# DEPDisc_Base_rev1_v4.net
KiCad netlist of a schematic drawn in EAGLE
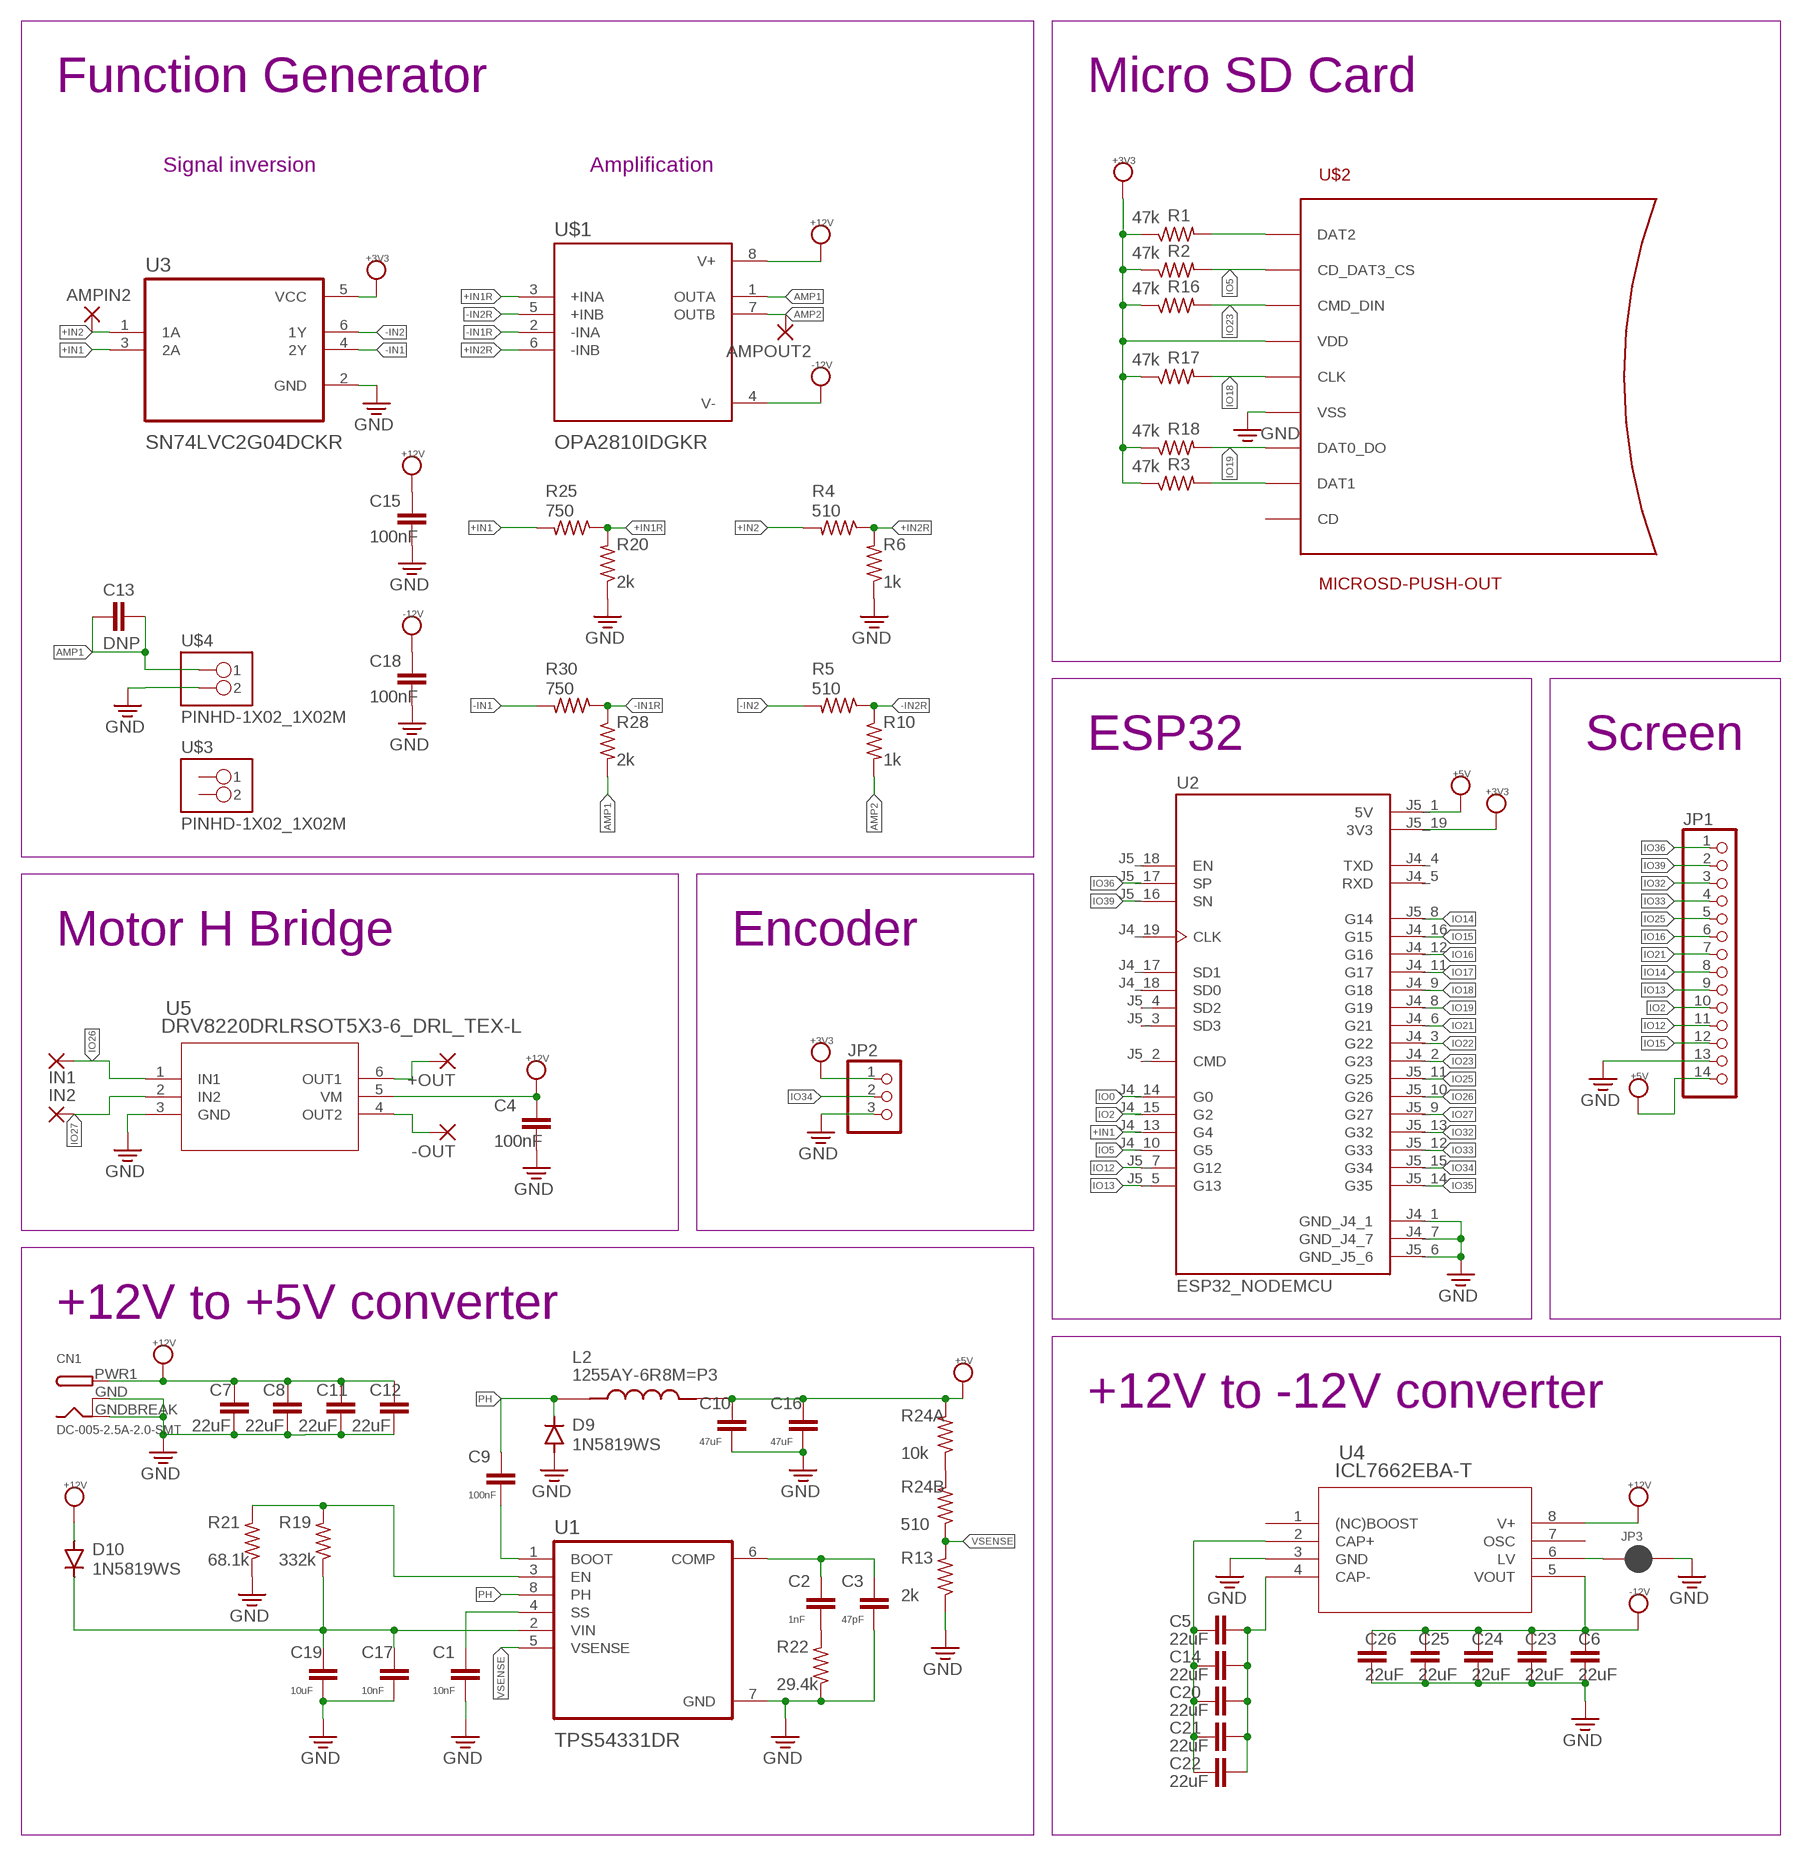
[diagram p0: schematic, sheet 1]

(export (version "E")
  (design (tool "Eeschema 10.0.6"))
  (components
    (comp (ref "+OUT")
      (value "2,54/1,1")
      (footprint "eagle-import:2,54_1,1")
      (libsource (lib "eagle-import") (part "2,54/1,1"))
    )
    (comp (ref "-OUT")
      (value "2,54/1,1")
      (footprint "eagle-import:2,54_1,1")
      (libsource (lib "eagle-import") (part "2,54/1,1"))
    )
    (comp (ref "AMPIN2")
      (value "1,6/0,8")
      (footprint "eagle-import:1,6_0,8")
      (libsource (lib "eagle-import") (part "1,6/0,8"))
    )
    (comp (ref "AMPOUT2")
      (value "1,6/0,8")
      (footprint "eagle-import:1,6_0,8")
      (libsource (lib "eagle-import") (part "1,6/0,8"))
    )
    (comp (ref "C1")
      (value "10nF")
      (footprint "eagle-import:C0603K")
      (libsource (lib "eagle-import") (part "resistor_348_C-EUC0603K"))
    )
    (comp (ref "C2")
      (value "1nF")
      (footprint "eagle-import:C0603K")
      (libsource (lib "eagle-import") (part "resistor_348_C-EUC0603K"))
    )
    (comp (ref "C3")
      (value "47pF")
      (footprint "eagle-import:C0603K")
      (libsource (lib "eagle-import") (part "resistor_348_C-EUC0603K"))
    )
    (comp (ref "C4")
      (value "100nF")
      (footprint "eagle-import:C0603K")
      (libsource (lib "eagle-import") (part "C-EUC0603K"))
    )
    (comp (ref "C5")
      (value "22uF")
      (footprint "eagle-import:C0805K")
      (libsource (lib "eagle-import") (part "C-EUC0805K"))
    )
    (comp (ref "C6")
      (value "22uF")
      (footprint "eagle-import:C0805K")
      (libsource (lib "eagle-import") (part "C-EUC0805K"))
    )
    (comp (ref "C7")
      (value "22uF")
      (footprint "eagle-import:C0805K")
      (libsource (lib "eagle-import") (part "C-EUC0805K"))
    )
    (comp (ref "C8")
      (value "22uF")
      (footprint "eagle-import:C0805K")
      (libsource (lib "eagle-import") (part "C-EUC0805K"))
    )
    (comp (ref "C9")
      (value "100nF")
      (footprint "eagle-import:C0603K")
      (libsource (lib "eagle-import") (part "resistor_348_C-EUC0603K"))
    )
    (comp (ref "C10")
      (value "47uF")
      (footprint "eagle-import:C0603K")
      (libsource (lib "eagle-import") (part "resistor_348_C-EUC0603K"))
    )
    (comp (ref "C11")
      (value "22uF")
      (footprint "eagle-import:C0805K")
      (libsource (lib "eagle-import") (part "C-EUC0805K"))
    )
    (comp (ref "C12")
      (value "22uF")
      (footprint "eagle-import:C0805K")
      (libsource (lib "eagle-import") (part "C-EUC0805K"))
    )
    (comp (ref "C13")
      (value "DNP")
      (footprint "eagle-import:C0805K")
      (libsource (lib "eagle-import") (part "resistor_348_C-EUC0805K"))
    )
    (comp (ref "C14")
      (value "22uF")
      (footprint "eagle-import:C0805K")
      (libsource (lib "eagle-import") (part "C-EUC0805K"))
    )
    (comp (ref "C15")
      (value "100nF")
      (footprint "eagle-import:C0603K")
      (libsource (lib "eagle-import") (part "C-EUC0603K"))
    )
    (comp (ref "C16")
      (value "47uF")
      (footprint "eagle-import:C0603K")
      (libsource (lib "eagle-import") (part "resistor_348_C-EUC0603K"))
    )
    (comp (ref "C17")
      (value "10nF")
      (footprint "eagle-import:C0603K")
      (libsource (lib "eagle-import") (part "resistor_348_C-EUC0603K"))
    )
    (comp (ref "C18")
      (value "100nF")
      (footprint "eagle-import:C0603K")
      (libsource (lib "eagle-import") (part "C-EUC0603K"))
    )
    (comp (ref "C19")
      (value "10uF")
      (footprint "eagle-import:C0603K")
      (libsource (lib "eagle-import") (part "resistor_348_C-EUC0603K"))
    )
    (comp (ref "C20")
      (value "22uF")
      (footprint "eagle-import:C0805K")
      (libsource (lib "eagle-import") (part "C-EUC0805K"))
    )
    (comp (ref "C21")
      (value "22uF")
      (footprint "eagle-import:C0805K")
      (libsource (lib "eagle-import") (part "C-EUC0805K"))
    )
    (comp (ref "C22")
      (value "22uF")
      (footprint "eagle-import:C0805K")
      (libsource (lib "eagle-import") (part "C-EUC0805K"))
    )
    (comp (ref "C23")
      (value "22uF")
      (footprint "eagle-import:C0805K")
      (libsource (lib "eagle-import") (part "C-EUC0805K"))
    )
    (comp (ref "C24")
      (value "22uF")
      (footprint "eagle-import:C0805K")
      (libsource (lib "eagle-import") (part "C-EUC0805K"))
    )
    (comp (ref "C25")
      (value "22uF")
      (footprint "eagle-import:C0805K")
      (libsource (lib "eagle-import") (part "C-EUC0805K"))
    )
    (comp (ref "C26")
      (value "22uF")
      (footprint "eagle-import:C0805K")
      (libsource (lib "eagle-import") (part "C-EUC0805K"))
    )
    (comp (ref "CN1")
      (value "DC-005-2.5A-2.0-SMT")
      (footprint "eagle-import:DCJACK_2MM_SMT")
      (libsource (lib "eagle-import") (part "DCBARRELSMT"))
    )
    (comp (ref "D9")
      (value "1N5819WS")
      (footprint "eagle-import:SOD323-W")
      (libsource (lib "eagle-import") (part "DIODE-SOD323-W"))
    )
    (comp (ref "D10")
      (value "1N5819WS")
      (footprint "eagle-import:SOD323-W")
      (libsource (lib "eagle-import") (part "DIODE-SOD323-W"))
    )
    (comp (ref "IN1")
      (value "2,54/1,1")
      (footprint "eagle-import:2,54_1,1")
      (libsource (lib "eagle-import") (part "2,54/1,1"))
    )
    (comp (ref "IN2")
      (value "2,54/1,1")
      (footprint "eagle-import:2,54_1,1")
      (libsource (lib "eagle-import") (part "2,54/1,1"))
    )
    (comp (ref "JP1")
      (value "PINHD-1X14")
      (footprint "eagle-import:1X14")
      (libsource (lib "eagle-import") (part "PINHD-1X14"))
    )
    (comp (ref "JP2")
      (value "PINHD-1X3")
      (footprint "eagle-import:1X03")
      (libsource (lib "eagle-import") (part "PINHD-1X3"))
    )
    (comp (ref "JP3")
      (value "JUMPER-SMT_2_NC_PASTE_SILK")
      (footprint "eagle-import:SMT-JUMPER_2_NC_PASTE_SILK")
      (libsource (lib "eagle-import") (part "JUMPER-SMT_2_NC_PASTE_SILK"))
    )
    (comp (ref "L2")
      (value "1255AY-6R8M=P3")
      (footprint "eagle-import:IND_1255AY-6R8M=P3")
      (fields (field (name "MF") "Murata Electronics"))
      (libsource (lib "eagle-import") (part "1255AY-6R8M=P3"))
    )
    (comp (ref "R1")
      (value "47k")
      (footprint "eagle-import:R0603")
      (libsource (lib "eagle-import") (part "R-US_R0603"))
    )
    (comp (ref "R2")
      (value "47k")
      (footprint "eagle-import:R0603")
      (libsource (lib "eagle-import") (part "R-US_R0603"))
    )
    (comp (ref "R3")
      (value "47k")
      (footprint "eagle-import:R0603")
      (libsource (lib "eagle-import") (part "R-US_R0603"))
    )
    (comp (ref "R4")
      (value "510")
      (footprint "eagle-import:R0603")
      (libsource (lib "eagle-import") (part "R-US_R0603"))
    )
    (comp (ref "R5")
      (value "510")
      (footprint "eagle-import:R0603")
      (libsource (lib "eagle-import") (part "R-US_R0603"))
    )
    (comp (ref "R6")
      (value "1k")
      (footprint "eagle-import:R0603")
      (libsource (lib "eagle-import") (part "R-US_R0603"))
    )
    (comp (ref "R10")
      (value "1k")
      (footprint "eagle-import:R0603")
      (libsource (lib "eagle-import") (part "R-US_R0603"))
    )
    (comp (ref "R13")
      (value "2k")
      (footprint "eagle-import:R0603")
      (libsource (lib "eagle-import") (part "R-US_R0603"))
    )
    (comp (ref "R16")
      (value "47k")
      (footprint "eagle-import:R0603")
      (libsource (lib "eagle-import") (part "R-US_R0603"))
    )
    (comp (ref "R17")
      (value "47k")
      (footprint "eagle-import:R0603")
      (libsource (lib "eagle-import") (part "R-US_R0603"))
    )
    (comp (ref "R18")
      (value "47k")
      (footprint "eagle-import:R0603")
      (libsource (lib "eagle-import") (part "R-US_R0603"))
    )
    (comp (ref "R19")
      (value "332k")
      (footprint "eagle-import:R0603")
      (libsource (lib "eagle-import") (part "R-US_R0603"))
    )
    (comp (ref "R20")
      (value "2k")
      (footprint "eagle-import:R0603")
      (libsource (lib "eagle-import") (part "R-US_R0603"))
    )
    (comp (ref "R21")
      (value "68.1k")
      (footprint "eagle-import:R0603")
      (libsource (lib "eagle-import") (part "R-US_R0603"))
    )
    (comp (ref "R22")
      (value "29.4k")
      (footprint "eagle-import:R0603")
      (libsource (lib "eagle-import") (part "R-US_R0603"))
    )
    (comp (ref "R24A")
      (value "10k")
      (footprint "eagle-import:R0603")
      (libsource (lib "eagle-import") (part "R-US_R0603"))
    )
    (comp (ref "R24B")
      (value "510")
      (footprint "eagle-import:R0603")
      (libsource (lib "eagle-import") (part "R-US_R0603"))
    )
    (comp (ref "R25")
      (value "750")
      (footprint "eagle-import:R0603")
      (libsource (lib "eagle-import") (part "R-US_R0603"))
    )
    (comp (ref "R28")
      (value "2k")
      (footprint "eagle-import:R0603")
      (libsource (lib "eagle-import") (part "R-US_R0603"))
    )
    (comp (ref "R30")
      (value "750")
      (footprint "eagle-import:R0603")
      (libsource (lib "eagle-import") (part "R-US_R0603"))
    )
    (comp (ref "U$1")
      (value "OPA2810IDGKR")
      (footprint "eagle-import:SOP65P490X110-8N")
      (fields (field (name "MOUSER_PART_NUMBER") "595-OPA2810IDGKR"))
      (libsource (lib "eagle-import") (part "OPA2810IDGKR"))
    )
    (comp (ref "U$2")
      (value "MICROSD-PUSH-OUT")
      (footprint "eagle-import:MICROSD-PUSH-OUT")
      (libsource (lib "eagle-import") (part "MICROSD-PUSH-OUT"))
    )
    (comp (ref "U$3")
      (value "PINHD-1X02_1X02M")
      (footprint "eagle-import:1X02")
      (libsource (lib "eagle-import") (part "PINHD-1X02_1X02M"))
    )
    (comp (ref "U$4")
      (value "PINHD-1X02_1X02M")
      (footprint "eagle-import:1X02")
      (libsource (lib "eagle-import") (part "PINHD-1X02_1X02M"))
    )
    (comp (ref "U1")
      (value "TPS54331DR")
      (footprint "eagle-import:SOIC127P599X175-8N")
      (fields (field (name "MF") "Texas Instruments"))
      (libsource (lib "eagle-import") (part "TPS54331DR"))
    )
    (comp (ref "U2")
      (value "ESP32_NODEMCU")
      (footprint "eagle-import:MODULE_ESP32_NODEMCU")
      (fields (field (name "MF") "AZ Delivery") (field (name "MP") "ESP32 NODEMCU"))
      (libsource (lib "eagle-import") (part "ESP32_NODEMCU"))
    )
    (comp (ref "U3")
      (value "SN74LVC2G04DCKR")
      (footprint "eagle-import:SOT65P210X110-6N")
      (fields (field (name "MF") "Texas Instruments"))
      (libsource (lib "eagle-import") (part "SN74LVC2G04DCKR"))
    )
    (comp (ref "U4")
      (value "ICL7662EBA-T")
      (footprint "eagle-import:21-0041B_8")
      (fields (field (name "MF") "Analog Devices") (field (name "MP") "ICL7662EBA+T"))
      (libsource (lib "eagle-import") (part "ICL7662EBA-T"))
    )
    (comp (ref "U5")
      (value "DRV8220DRLRSOT5X3-6_DRL_TEX-L")
      (footprint "eagle-import:SOT5X3-6_DRL_TEX-L")
      (fields
        (field (name "MANUFACTURER_PART_NUMBER") "DRV8220DRLR")
        (field (name "COPYRIGHT") "Copyright (C) 2024 Ultra Librarian. All rights reserved.")
      )
      (libsource (lib "eagle-import") (part "DRV8220DRLRSOT5X3-6_DRL_TEX-L"))
    )
  )
  (nets
    (net (code "1") (name "+3V3") (class "Default")
      (node (ref "JP2") (pin "1") (pinfunction "1_1") (pintype "passive"))
      (node (ref "R1") (pin "1") (pinfunction "1_1") (pintype "passive"))
      (node (ref "R16") (pin "1") (pinfunction "1_1") (pintype "passive"))
      (node (ref "R17") (pin "1") (pinfunction "1_1") (pintype "passive"))
      (node (ref "R18") (pin "1") (pinfunction "1_1") (pintype "passive"))
      (node (ref "R2") (pin "1") (pinfunction "1_1") (pintype "passive"))
      (node (ref "R3") (pin "1") (pinfunction "1_1") (pintype "passive"))
      (node (ref "U$2") (pin "4") (pinfunction "VDD_4") (pintype "bidirectional"))
      (node (ref "U2") (pin "J5_19") (pinfunction "3V3_J5_19") (pintype "power_in"))
      (node (ref "U3") (pin "5") (pinfunction "VCC_5") (pintype "power_in"))
    )
    (net (code "2") (name "+5V") (class "Default")
      (node (ref "C10") (pin "1") (pinfunction "1_1") (pintype "passive"))
      (node (ref "C16") (pin "1") (pinfunction "1_1") (pintype "passive"))
      (node (ref "JP1") (pin "14") (pinfunction "14_14") (pintype "passive"))
      (node (ref "L2") (pin "2") (pinfunction "2_2") (pintype "passive"))
      (node (ref "R24A") (pin "2") (pinfunction "2_2") (pintype "passive"))
      (node (ref "U2") (pin "J5_1") (pinfunction "5V_J5_1") (pintype "power_in"))
    )
    (net (code "3") (name "+12V") (class "Default")
      (node (ref "C11") (pin "2") (pinfunction "2_2") (pintype "passive"))
      (node (ref "C12") (pin "2") (pinfunction "2_2") (pintype "passive"))
      (node (ref "C15") (pin "1") (pinfunction "1_1") (pintype "passive"))
      (node (ref "C4") (pin "1") (pinfunction "1_1") (pintype "passive"))
      (node (ref "C7") (pin "2") (pinfunction "2_2") (pintype "passive"))
      (node (ref "C8") (pin "2") (pinfunction "2_2") (pintype "passive"))
      (node (ref "CN1") (pin "PWR1") (pinfunction "PWR_PWR1") (pintype "power_in"))
      (node (ref "D10") (pin "A") (pinfunction "A_A") (pintype "passive"))
      (node (ref "U$1") (pin "8") (pinfunction "V+_8") (pintype "bidirectional"))
      (node (ref "U4") (pin "8") (pinfunction "V+_8") (pintype "power_in"))
      (node (ref "U5") (pin "5") (pinfunction "VM_5") (pintype "power_in"))
    )
    (net (code "4") (name "+IN1") (class "Default")
      (node (ref "R25") (pin "2") (pinfunction "2_2") (pintype "passive"))
      (node (ref "U2") (pin "J4_13") (pinfunction "G4_J4_13") (pintype "bidirectional"))
      (node (ref "U3") (pin "3") (pinfunction "2A_3") (pintype "input"))
    )
    (net (code "5") (name "+IN1R") (class "Default")
      (node (ref "R20") (pin "2") (pinfunction "2_2") (pintype "passive"))
      (node (ref "R25") (pin "1") (pinfunction "1_1") (pintype "passive"))
      (node (ref "U$1") (pin "3") (pinfunction "+INA_3") (pintype "bidirectional"))
    )
    (net (code "6") (name "+IN2") (class "Default")
      (node (ref "AMPIN2") (pin "1") (pinfunction "P_1") (pintype "passive"))
      (node (ref "R4") (pin "2") (pinfunction "2_2") (pintype "passive"))
      (node (ref "U3") (pin "1") (pinfunction "1A_1") (pintype "input"))
    )
    (net (code "7") (name "+IN2R") (class "Default")
      (node (ref "R4") (pin "1") (pinfunction "1_1") (pintype "passive"))
      (node (ref "R6") (pin "2") (pinfunction "2_2") (pintype "passive"))
      (node (ref "U$1") (pin "6") (pinfunction "-INB_6") (pintype "bidirectional"))
    )
    (net (code "8") (name "-12V") (class "Default")
      (node (ref "C18") (pin "1") (pinfunction "1_1") (pintype "passive"))
      (node (ref "C23") (pin "2") (pinfunction "2_2") (pintype "passive"))
      (node (ref "C24") (pin "2") (pinfunction "2_2") (pintype "passive"))
      (node (ref "C25") (pin "2") (pinfunction "2_2") (pintype "passive"))
      (node (ref "C26") (pin "2") (pinfunction "2_2") (pintype "passive"))
      (node (ref "C6") (pin "2") (pinfunction "2_2") (pintype "passive"))
      (node (ref "U$1") (pin "4") (pinfunction "V-_4") (pintype "bidirectional"))
      (node (ref "U4") (pin "5") (pinfunction "VOUT_5") (pintype "output"))
    )
    (net (code "9") (name "-IN1") (class "Default")
      (node (ref "R30") (pin "2") (pinfunction "2_2") (pintype "passive"))
      (node (ref "U3") (pin "4") (pinfunction "2Y_4") (pintype "output"))
    )
    (net (code "10") (name "-IN1R") (class "Default")
      (node (ref "R28") (pin "1") (pinfunction "1_1") (pintype "passive"))
      (node (ref "R30") (pin "1") (pinfunction "1_1") (pintype "passive"))
      (node (ref "U$1") (pin "2") (pinfunction "-INA_2") (pintype "bidirectional"))
    )
    (net (code "11") (name "-IN2") (class "Default")
      (node (ref "R5") (pin "2") (pinfunction "2_2") (pintype "passive"))
      (node (ref "U3") (pin "6") (pinfunction "1Y_6") (pintype "output"))
    )
    (net (code "12") (name "-IN2R") (class "Default")
      (node (ref "R10") (pin "1") (pinfunction "1_1") (pintype "passive"))
      (node (ref "R5") (pin "1") (pinfunction "1_1") (pintype "passive"))
      (node (ref "U$1") (pin "5") (pinfunction "+INB_5") (pintype "bidirectional"))
    )
    (net (code "13") (name "AMP1") (class "Default")
      (node (ref "C13") (pin "1") (pinfunction "1_1") (pintype "passive"))
      (node (ref "C13") (pin "2") (pinfunction "2_2") (pintype "passive"))
      (node (ref "R28") (pin "2") (pinfunction "2_2") (pintype "passive"))
      (node (ref "U$1") (pin "1") (pinfunction "OUTA_1") (pintype "bidirectional"))
      (node (ref "U$4") (pin "1") (pinfunction "1_1") (pintype "bidirectional"))
    )
    (net (code "14") (name "AMP2") (class "Default")
      (node (ref "AMPOUT2") (pin "1") (pinfunction "P_1") (pintype "passive"))
      (node (ref "R10") (pin "2") (pinfunction "2_2") (pintype "passive"))
      (node (ref "U$1") (pin "7") (pinfunction "OUTB_7") (pintype "bidirectional"))
    )
    (net (code "15") (name "GND") (class "Default")
      (node (ref "C1") (pin "2") (pinfunction "2_2") (pintype "passive"))
      (node (ref "C10") (pin "2") (pinfunction "2_2") (pintype "passive"))
      (node (ref "C11") (pin "1") (pinfunction "1_1") (pintype "passive"))
      (node (ref "C12") (pin "1") (pinfunction "1_1") (pintype "passive"))
      (node (ref "C15") (pin "2") (pinfunction "2_2") (pintype "passive"))
      (node (ref "C16") (pin "2") (pinfunction "2_2") (pintype "passive"))
      (node (ref "C17") (pin "2") (pinfunction "2_2") (pintype "passive"))
      (node (ref "C18") (pin "2") (pinfunction "2_2") (pintype "passive"))
      (node (ref "C19") (pin "2") (pinfunction "2_2") (pintype "passive"))
      (node (ref "C23") (pin "1") (pinfunction "1_1") (pintype "passive"))
      (node (ref "C24") (pin "1") (pinfunction "1_1") (pintype "passive"))
      (node (ref "C25") (pin "1") (pinfunction "1_1") (pintype "passive"))
      (node (ref "C26") (pin "1") (pinfunction "1_1") (pintype "passive"))
      (node (ref "C3") (pin "2") (pinfunction "2_2") (pintype "passive"))
      (node (ref "C4") (pin "2") (pinfunction "2_2") (pintype "passive"))
      (node (ref "C6") (pin "1") (pinfunction "1_1") (pintype "passive"))
      (node (ref "C7") (pin "1") (pinfunction "1_1") (pintype "passive"))
      (node (ref "C8") (pin "1") (pinfunction "1_1") (pintype "passive"))
      (node (ref "CN1") (pin "GND") (pinfunction "GNDBREAK_GND") (pintype "power_in"))
      (node (ref "CN1") (pin "GNDBREAK") (pinfunction "GND_GNDBREAK") (pintype "power_in"))
      (node (ref "D9") (pin "A") (pinfunction "A_A") (pintype "passive"))
      (node (ref "JP1") (pin "13") (pinfunction "13_13") (pintype "passive"))
      (node (ref "JP2") (pin "3") (pinfunction "3_3") (pintype "passive"))
      (node (ref "JP3") (pin "2") (pinfunction "2_2") (pintype "passive"))
      (node (ref "R13") (pin "1") (pinfunction "1_1") (pintype "passive"))
      (node (ref "R20") (pin "1") (pinfunction "1_1") (pintype "passive"))
      (node (ref "R21") (pin "1") (pinfunction "1_1") (pintype "passive"))
      (node (ref "R22") (pin "1") (pinfunction "1_1") (pintype "passive"))
      (node (ref "R6") (pin "1") (pinfunction "1_1") (pintype "passive"))
      (node (ref "U$2") (pin "6") (pinfunction "VSS_6") (pintype "bidirectional"))
      (node (ref "U$2") (pin "G1") (pinfunction "VSS_G1") (pintype "bidirectional"))
      (node (ref "U$2") (pin "G2") (pinfunction "VSS_G2") (pintype "bidirectional"))
      (node (ref "U$2") (pin "G3") (pinfunction "VSS_G3") (pintype "bidirectional"))
      (node (ref "U$2") (pin "G4") (pinfunction "VSS_G4") (pintype "bidirectional"))
      (node (ref "U$4") (pin "2") (pinfunction "2_2") (pintype "bidirectional"))
      (node (ref "U1") (pin "7") (pinfunction "GND_7") (pintype "power_in"))
      (node (ref "U2") (pin "J4_1") (pinfunction "GND_J4_1_J4_1") (pintype "power_in"))
      (node (ref "U2") (pin "J4_7") (pinfunction "GND_J4_7_J4_7") (pintype "power_in"))
      (node (ref "U2") (pin "J5_6") (pinfunction "GND_J5_6_J5_6") (pintype "power_in"))
      (node (ref "U3") (pin "2") (pinfunction "GND_2") (pintype "power_in"))
      (node (ref "U4") (pin "3") (pinfunction "GND_3") (pintype "power_in"))
      (node (ref "U5") (pin "3") (pinfunction "GND_3") (pintype "passive"))
    )
    (net (code "16") (name "IO0") (class "Default")
      (node (ref "U2") (pin "J4_14") (pinfunction "G0_J4_14") (pintype "bidirectional"))
    )
    (net (code "17") (name "IO2") (class "Default")
      (node (ref "JP1") (pin "10") (pinfunction "10_10") (pintype "passive"))
      (node (ref "U2") (pin "J4_15") (pinfunction "G2_J4_15") (pintype "bidirectional"))
    )
    (net (code "18") (name "IO5") (class "Default")
      (node (ref "R2") (pin "2") (pinfunction "2_2") (pintype "passive"))
      (node (ref "U$2") (pin "2") (pinfunction "CD_DAT3_CS_2") (pintype "bidirectional"))
      (node (ref "U2") (pin "J4_10") (pinfunction "G5_J4_10") (pintype "bidirectional"))
    )
    (net (code "19") (name "IO12") (class "Default")
      (node (ref "JP1") (pin "11") (pinfunction "11_11") (pintype "passive"))
      (node (ref "U2") (pin "J5_7") (pinfunction "G12_J5_7") (pintype "bidirectional"))
    )
    (net (code "20") (name "IO13") (class "Default")
      (node (ref "JP1") (pin "9") (pinfunction "9_9") (pintype "passive"))
      (node (ref "U2") (pin "J5_5") (pinfunction "G13_J5_5") (pintype "bidirectional"))
    )
    (net (code "21") (name "IO14") (class "Default")
      (node (ref "JP1") (pin "8") (pinfunction "8_8") (pintype "passive"))
      (node (ref "U2") (pin "J5_8") (pinfunction "G14_J5_8") (pintype "bidirectional"))
    )
    (net (code "22") (name "IO15") (class "Default")
      (node (ref "JP1") (pin "12") (pinfunction "12_12") (pintype "passive"))
      (node (ref "U2") (pin "J4_16") (pinfunction "G15_J4_16") (pintype "bidirectional"))
    )
    (net (code "23") (name "IO16") (class "Default")
      (node (ref "JP1") (pin "6") (pinfunction "6_6") (pintype "passive"))
      (node (ref "U2") (pin "J4_12") (pinfunction "G16_J4_12") (pintype "bidirectional"))
    )
    (net (code "24") (name "IO17") (class "Default")
      (node (ref "U2") (pin "J4_11") (pinfunction "G17_J4_11") (pintype "bidirectional"))
    )
    (net (code "25") (name "IO18") (class "Default")
      (node (ref "R17") (pin "2") (pinfunction "2_2") (pintype "passive"))
      (node (ref "U$2") (pin "5") (pinfunction "CLK_5") (pintype "bidirectional"))
      (node (ref "U2") (pin "J4_9") (pinfunction "G18_J4_9") (pintype "bidirectional"))
    )
    (net (code "26") (name "IO19") (class "Default")
      (node (ref "R18") (pin "2") (pinfunction "2_2") (pintype "passive"))
      (node (ref "U$2") (pin "7") (pinfunction "DAT0_DO_7") (pintype "bidirectional"))
      (node (ref "U2") (pin "J4_8") (pinfunction "G19_J4_8") (pintype "bidirectional"))
    )
    (net (code "27") (name "IO21") (class "Default")
      (node (ref "JP1") (pin "7") (pinfunction "7_7") (pintype "passive"))
      (node (ref "U2") (pin "J4_6") (pinfunction "G21_J4_6") (pintype "bidirectional"))
    )
    (net (code "28") (name "IO22") (class "Default")
      (node (ref "U2") (pin "J4_3") (pinfunction "G22_J4_3") (pintype "bidirectional"))
    )
    (net (code "29") (name "IO23") (class "Default")
      (node (ref "R16") (pin "2") (pinfunction "2_2") (pintype "passive"))
      (node (ref "U$2") (pin "3") (pinfunction "CMD_DIN_3") (pintype "bidirectional"))
      (node (ref "U2") (pin "J4_2") (pinfunction "G23_J4_2") (pintype "bidirectional"))
    )
    (net (code "30") (name "IO25") (class "Default")
      (node (ref "JP1") (pin "5") (pinfunction "5_5") (pintype "passive"))
      (node (ref "U2") (pin "J5_11") (pinfunction "G25_J5_11") (pintype "bidirectional"))
    )
    (net (code "31") (name "IO26") (class "Default")
      (node (ref "IN1") (pin "1") (pinfunction "P_1") (pintype "passive"))
      (node (ref "U2") (pin "J5_10") (pinfunction "G26_J5_10") (pintype "bidirectional"))
      (node (ref "U5") (pin "1") (pinfunction "IN1_1") (pintype "input"))
    )
    (net (code "32") (name "IO27") (class "Default")
      (node (ref "IN2") (pin "1") (pinfunction "P_1") (pintype "passive"))
      (node (ref "U2") (pin "J5_9") (pinfunction "G27_J5_9") (pintype "bidirectional"))
      (node (ref "U5") (pin "2") (pinfunction "IN2_2") (pintype "input"))
    )
    (net (code "33") (name "IO32") (class "Default")
      (node (ref "JP1") (pin "3") (pinfunction "3_3") (pintype "passive"))
      (node (ref "U2") (pin "J5_13") (pinfunction "G32_J5_13") (pintype "bidirectional"))
    )
    (net (code "34") (name "IO33") (class "Default")
      (node (ref "JP1") (pin "4") (pinfunction "4_4") (pintype "passive"))
      (node (ref "U2") (pin "J5_12") (pinfunction "G33_J5_12") (pintype "bidirectional"))
    )
    (net (code "35") (name "IO34") (class "Default")
      (node (ref "JP2") (pin "2") (pinfunction "2_2") (pintype "passive"))
      (node (ref "U2") (pin "J5_15") (pinfunction "G34_J5_15") (pintype "bidirectional"))
    )
    (net (code "36") (name "IO35") (class "Default")
      (node (ref "U2") (pin "J5_14") (pinfunction "G35_J5_14") (pintype "bidirectional"))
    )
    (net (code "37") (name "IO36") (class "Default")
      (node (ref "JP1") (pin "1") (pinfunction "1_1") (pintype "passive"))
      (node (ref "U2") (pin "J5_17") (pinfunction "SP_J5_17") (pintype "input"))
    )
    (net (code "38") (name "IO39") (class "Default")
      (node (ref "JP1") (pin "2") (pinfunction "2_2") (pintype "passive"))
      (node (ref "U2") (pin "J5_16") (pinfunction "SN_J5_16") (pintype "input"))
    )
    (net (code "39") (name "Net-(+OUT-P)") (class "Default")
      (node (ref "+OUT") (pin "1") (pinfunction "P_1") (pintype "passive"))
      (node (ref "U5") (pin "6") (pinfunction "OUT1_6") (pintype "output"))
    )
    (net (code "40") (name "Net-(-OUT-P)") (class "Default")
      (node (ref "-OUT") (pin "1") (pinfunction "P_1") (pintype "passive"))
      (node (ref "U5") (pin "4") (pinfunction "OUT2_4") (pintype "output"))
    )
    (net (code "41") (name "Net-(C2-Pad2)") (class "Default")
      (node (ref "C2") (pin "2") (pinfunction "2_2") (pintype "passive"))
      (node (ref "R22") (pin "2") (pinfunction "2_2") (pintype "passive"))
    )
    (net (code "42") (name "Net-(R24A-Pad1)") (class "Default")
      (node (ref "R24A") (pin "1") (pinfunction "1_1") (pintype "passive"))
      (node (ref "R24B") (pin "2") (pinfunction "2_2") (pintype "passive"))
    )
    (net (code "43") (name "Net-(U$2-DAT1)") (class "Default")
      (node (ref "R3") (pin "2") (pinfunction "2_2") (pintype "passive"))
      (node (ref "U$2") (pin "8") (pinfunction "DAT1_8") (pintype "bidirectional"))
    )
    (net (code "44") (name "Net-(U$2-DAT2)") (class "Default")
      (node (ref "R1") (pin "2") (pinfunction "2_2") (pintype "passive"))
      (node (ref "U$2") (pin "1") (pinfunction "DAT2_1") (pintype "bidirectional"))
    )
    (net (code "45") (name "Net-(U1-BOOT)") (class "Default")
      (node (ref "C9") (pin "2") (pinfunction "2_2") (pintype "passive"))
      (node (ref "U1") (pin "1") (pinfunction "BOOT_1") (pintype "input"))
    )
    (net (code "46") (name "Net-(U1-COMP)") (class "Default")
      (node (ref "C2") (pin "1") (pinfunction "1_1") (pintype "passive"))
      (node (ref "C3") (pin "1") (pinfunction "1_1") (pintype "passive"))
      (node (ref "U1") (pin "6") (pinfunction "COMP_6") (pintype "output"))
    )
    (net (code "47") (name "Net-(U1-EN)") (class "Default")
      (node (ref "R19") (pin "2") (pinfunction "2_2") (pintype "passive"))
      (node (ref "R21") (pin "2") (pinfunction "2_2") (pintype "passive"))
      (node (ref "U1") (pin "3") (pinfunction "EN_3") (pintype "input"))
    )
    (net (code "48") (name "Net-(U1-SS)") (class "Default")
      (node (ref "C1") (pin "1") (pinfunction "1_1") (pintype "passive"))
      (node (ref "U1") (pin "4") (pinfunction "SS_4") (pintype "input"))
    )
    (net (code "49") (name "Net-(U1-VIN)") (class "Default")
      (node (ref "C17") (pin "1") (pinfunction "1_1") (pintype "passive"))
      (node (ref "C19") (pin "1") (pinfunction "1_1") (pintype "passive"))
      (node (ref "D10") (pin "C") (pinfunction "C_C") (pintype "passive"))
      (node (ref "R19") (pin "1") (pinfunction "1_1") (pintype "passive"))
      (node (ref "U1") (pin "2") (pinfunction "VIN_2") (pintype "input"))
    )
    (net (code "50") (name "Net-(U4-CAP+)") (class "Default")
      (node (ref "C14") (pin "2") (pinfunction "2_2") (pintype "passive"))
      (node (ref "C20") (pin "2") (pinfunction "2_2") (pintype "passive"))
      (node (ref "C21") (pin "2") (pinfunction "2_2") (pintype "passive"))
      (node (ref "C22") (pin "2") (pinfunction "2_2") (pintype "passive"))
      (node (ref "C5") (pin "2") (pinfunction "2_2") (pintype "passive"))
      (node (ref "U4") (pin "2") (pinfunction "CAP+_2") (pintype "passive"))
    )
    (net (code "51") (name "Net-(U4-CAP-)") (class "Default")
      (node (ref "C14") (pin "1") (pinfunction "1_1") (pintype "passive"))
      (node (ref "C20") (pin "1") (pinfunction "1_1") (pintype "passive"))
      (node (ref "C21") (pin "1") (pinfunction "1_1") (pintype "passive"))
      (node (ref "C22") (pin "1") (pinfunction "1_1") (pintype "passive"))
      (node (ref "C5") (pin "1") (pinfunction "1_1") (pintype "passive"))
      (node (ref "U4") (pin "4") (pinfunction "CAP-_4") (pintype "passive"))
    )
    (net (code "52") (name "Net-(U4-LV)") (class "Default")
      (node (ref "JP3") (pin "1") (pinfunction "1_1") (pintype "passive"))
      (node (ref "U4") (pin "6") (pinfunction "LV_6") (pintype "passive"))
    )
    (net (code "53") (name "PH") (class "Default")
      (node (ref "C9") (pin "1") (pinfunction "1_1") (pintype "passive"))
      (node (ref "D9") (pin "C") (pinfunction "C_C") (pintype "passive"))
      (node (ref "L2") (pin "1") (pinfunction "1_1") (pintype "passive"))
      (node (ref "U1") (pin "8") (pinfunction "PH_8") (pintype "input"))
    )
    (net (code "54") (name "VSENSE") (class "Default")
      (node (ref "R13") (pin "2") (pinfunction "2_2") (pintype "passive"))
      (node (ref "R24B") (pin "1") (pinfunction "1_1") (pintype "passive"))
      (node (ref "U1") (pin "5") (pinfunction "VSENSE_5") (pintype "input"))
    )
    (net (code "55") (name "unconnected-(U$2-PadCD)") (class "Default")
      (node (ref "U$2") (pin "CD") (pinfunction "CD_CD") (pintype "bidirectional"))
    )
    (net (code "56") (name "unconnected-(U$3-Pad1)") (class "Default")
      (node (ref "U$3") (pin "1") (pinfunction "1_1") (pintype "bidirectional"))
    )
    (net (code "57") (name "unconnected-(U$3-Pad2)") (class "Default")
      (node (ref "U$3") (pin "2") (pinfunction "2_2") (pintype "bidirectional"))
    )
    (net (code "58") (name "unconnected-(U2-CLK-PadJ4_19)") (class "Default")
      (node (ref "U2") (pin "J4_19") (pinfunction "CLK_J4_19") (pintype "input"))
    )
    (net (code "59") (name "unconnected-(U2-CMD-PadJ5_2)") (class "Default")
      (node (ref "U2") (pin "J5_2") (pinfunction "CMD_J5_2") (pintype "bidirectional"))
    )
    (net (code "60") (name "unconnected-(U2-EN-PadJ5_18)") (class "Default")
      (node (ref "U2") (pin "J5_18") (pinfunction "EN_J5_18") (pintype "input"))
    )
    (net (code "61") (name "unconnected-(U2-RXD-PadJ4_5)") (class "Default")
      (node (ref "U2") (pin "J4_5") (pinfunction "RXD_J4_5") (pintype "input"))
    )
    (net (code "62") (name "unconnected-(U2-SD0-PadJ4_18)") (class "Default")
      (node (ref "U2") (pin "J4_18") (pinfunction "SD0_J4_18") (pintype "bidirectional"))
    )
    (net (code "63") (name "unconnected-(U2-SD1-PadJ4_17)") (class "Default")
      (node (ref "U2") (pin "J4_17") (pinfunction "SD1_J4_17") (pintype "bidirectional"))
    )
    (net (code "64") (name "unconnected-(U2-SD2-PadJ5_4)") (class "Default")
      (node (ref "U2") (pin "J5_4") (pinfunction "SD2_J5_4") (pintype "bidirectional"))
    )
    (net (code "65") (name "unconnected-(U2-SD3-PadJ5_3)") (class "Default")
      (node (ref "U2") (pin "J5_3") (pinfunction "SD3_J5_3") (pintype "bidirectional"))
    )
    (net (code "66") (name "unconnected-(U2-TXD-PadJ4_4)") (class "Default")
      (node (ref "U2") (pin "J4_4") (pinfunction "TXD_J4_4") (pintype "output"))
    )
    (net (code "67") (name "unconnected-(U4-(NC)BOOST-Pad1)") (class "Default")
      (node (ref "U4") (pin "1") (pinfunction "(NC)BOOST_1") (pintype "passive"))
    )
    (net (code "68") (name "unconnected-(U4-OSC-Pad7)") (class "Default")
      (node (ref "U4") (pin "7") (pinfunction "OSC_7") (pintype "passive"))
    )
  )
)
